# PCBNewLdo.net
KiCad netlist of a schematic drawn in EAGLE
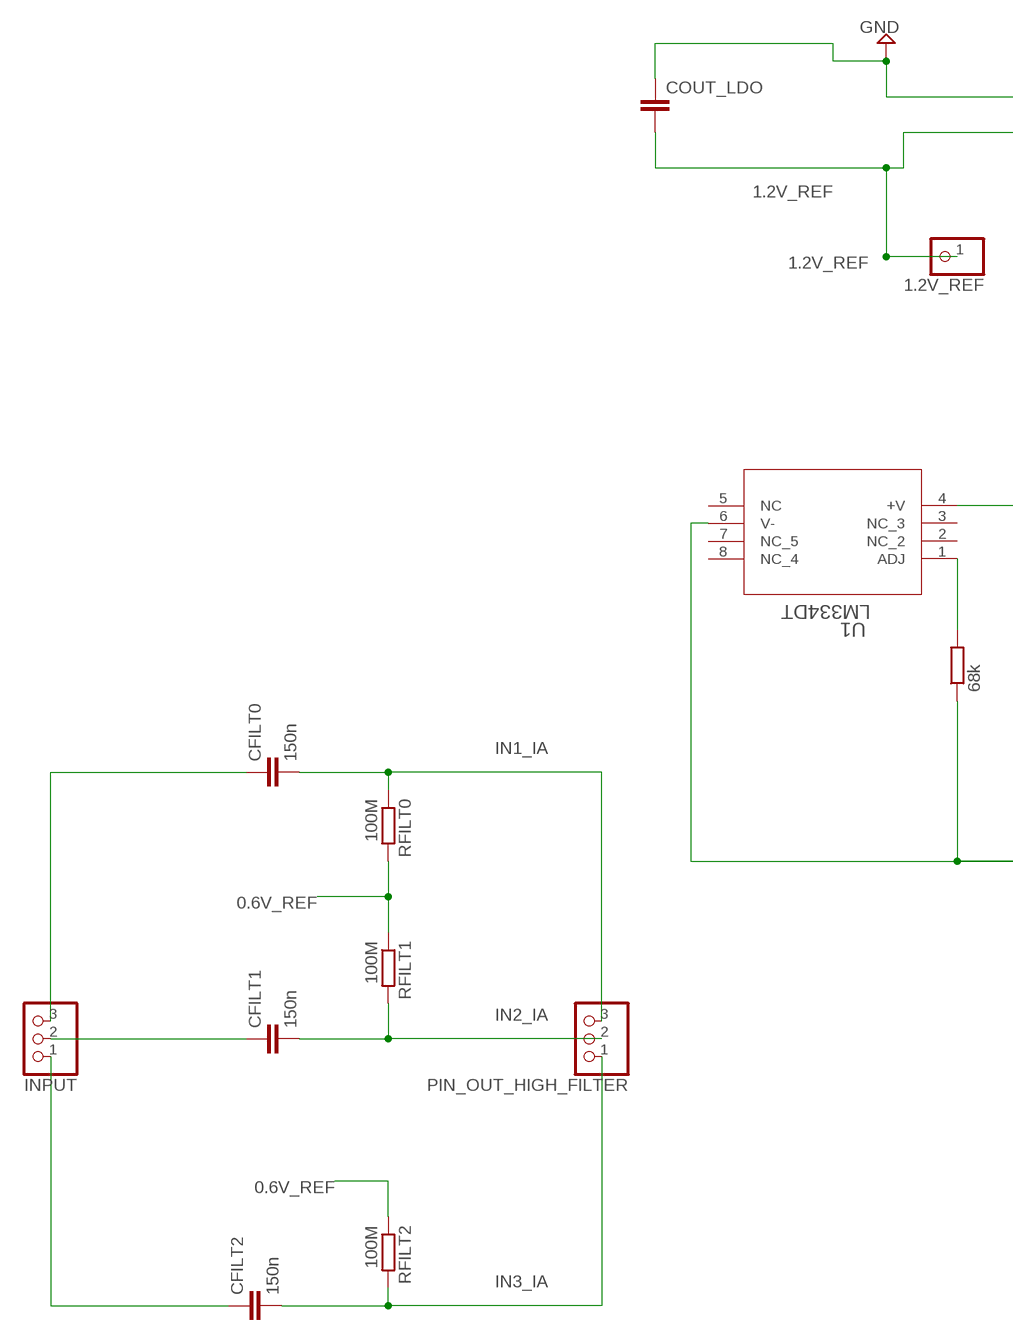
[diagram p0: schematic, sheet 1, part 1 of 2]
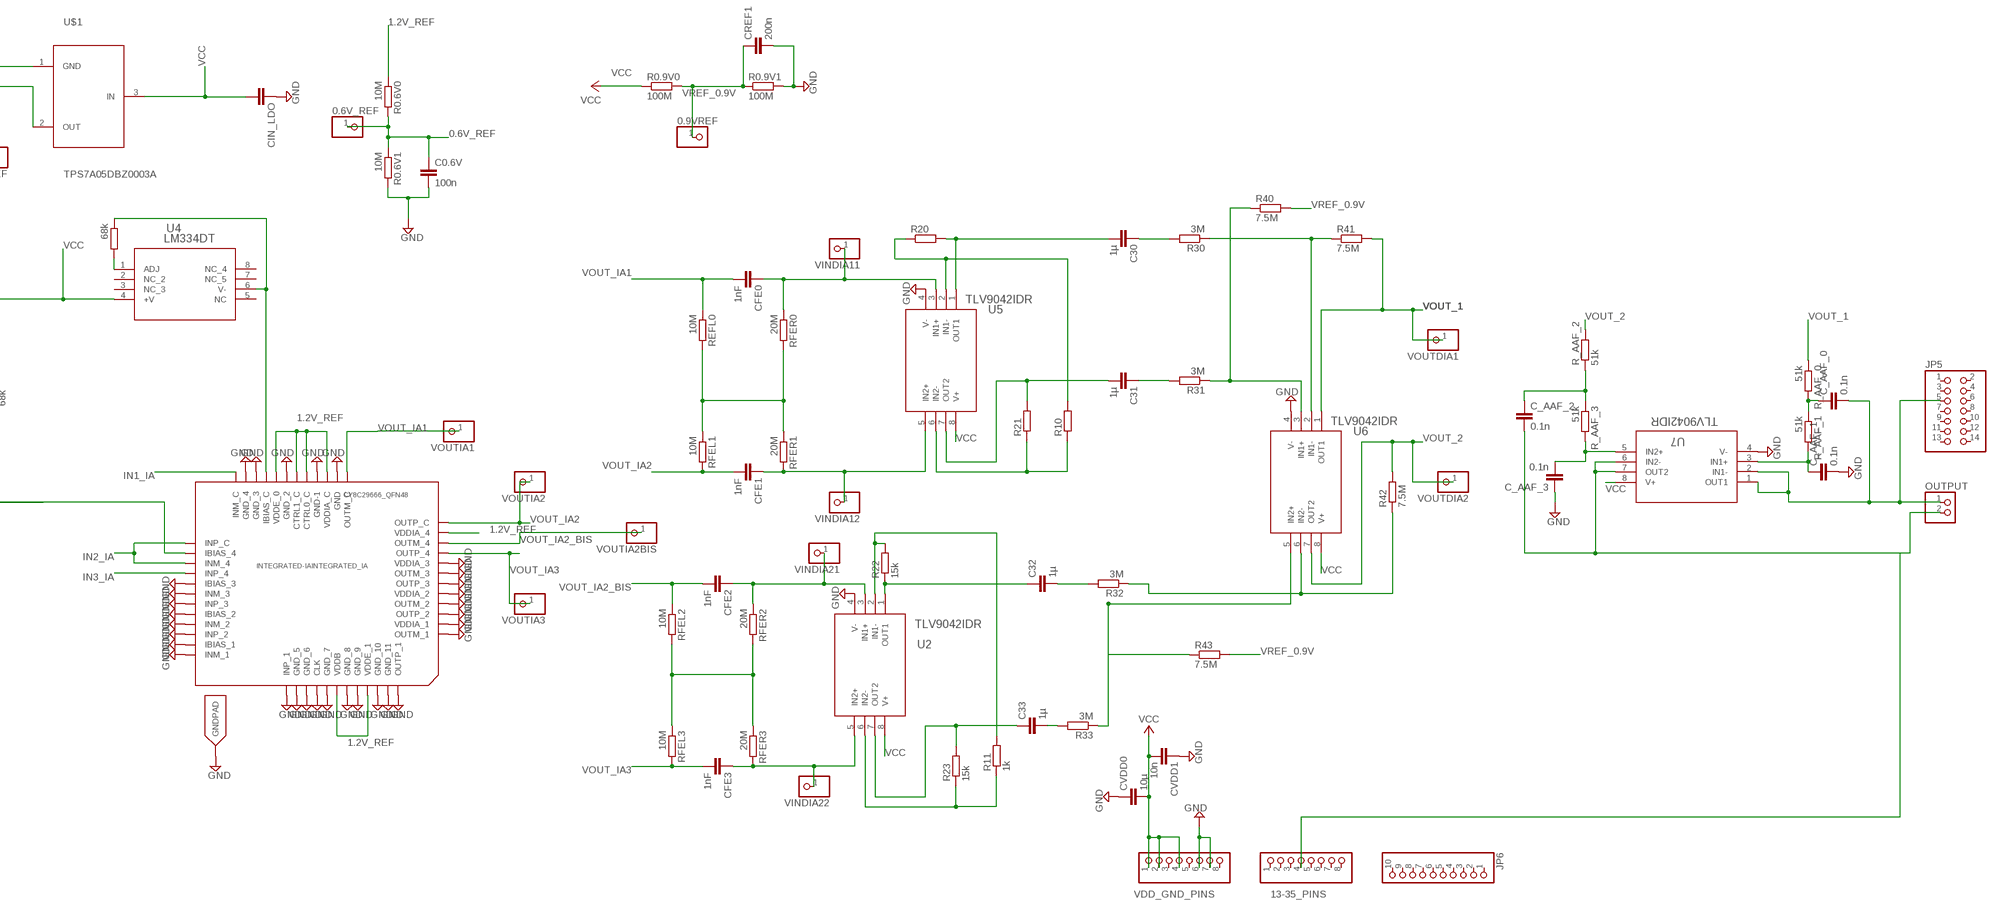
[diagram p1: schematic, sheet 1, part 2 of 2]

(export (version "E")
  (design (tool "Eeschema 10.0.6"))
  (components
    (comp (ref "0.6V_REF")
      (value "PINHD-1X1")
      (footprint "eagle-import:1X01")
      (libsource (lib "eagle-import") (part "PINHD-1X1"))
    )
    (comp (ref "0.9VREF")
      (value "PINHD-1X1")
      (footprint "eagle-import:1X01")
      (libsource (lib "eagle-import") (part "PINHD-1X1"))
    )
    (comp (ref "1.2V_REF")
      (value "PINHD-1X1")
      (footprint "eagle-import:1X01")
      (libsource (lib "eagle-import") (part "PINHD-1X1"))
    )
    (comp (ref "13-35_PINS")
      (value "PINHD-1X8")
      (footprint "eagle-import:1X08")
      (libsource (lib "eagle-import") (part "PINHD-1X8"))
    )
    (comp (ref "C0.6V")
      (value "100n")
      (footprint "eagle-import:C0603")
      (libsource (lib "eagle-import") (part "C-EUC0603"))
    )
    (comp (ref "C30")
      (value "1µ")
      (footprint "eagle-import:C0603")
      (libsource (lib "eagle-import") (part "C-EUC0603"))
    )
    (comp (ref "C31")
      (value "1µ")
      (footprint "eagle-import:C0603")
      (libsource (lib "eagle-import") (part "C-EUC0603"))
    )
    (comp (ref "C32")
      (value "1µ")
      (footprint "eagle-import:C0603")
      (libsource (lib "eagle-import") (part "C-EUC0603"))
    )
    (comp (ref "C33")
      (value "1µ")
      (footprint "eagle-import:C0603")
      (libsource (lib "eagle-import") (part "C-EUC0603"))
    )
    (comp (ref "CFE0")
      (value "1nF")
      (footprint "eagle-import:C0603")
      (libsource (lib "eagle-import") (part "C-EUC0603"))
    )
    (comp (ref "CFE1")
      (value "1nF")
      (footprint "eagle-import:C0603")
      (libsource (lib "eagle-import") (part "C-EUC0603"))
    )
    (comp (ref "CFE2")
      (value "1nF")
      (footprint "eagle-import:C0603")
      (libsource (lib "eagle-import") (part "C-EUC0603"))
    )
    (comp (ref "CFE3")
      (value "1nF")
      (footprint "eagle-import:C0603")
      (libsource (lib "eagle-import") (part "C-EUC0603"))
    )
    (comp (ref "CFILT0")
      (value "150n")
      (footprint "eagle-import:C0603")
      (libsource (lib "eagle-import") (part "C-EUC0603"))
    )
    (comp (ref "CFILT1")
      (value "150n")
      (footprint "eagle-import:C0603")
      (libsource (lib "eagle-import") (part "C-EUC0603"))
    )
    (comp (ref "CFILT2")
      (value "150n")
      (footprint "eagle-import:C0603")
      (libsource (lib "eagle-import") (part "C-EUC0603"))
    )
    (comp (ref "CIN_LDO")
      (value "1µ")
      (footprint "eagle-import:C0603")
      (libsource (lib "eagle-import") (part "C-EUC0603"))
    )
    (comp (ref "COUT_LDO")
      (value "4.7µ")
      (footprint "eagle-import:C0603")
      (libsource (lib "eagle-import") (part "C-EUC0603"))
    )
    (comp (ref "CREF1")
      (value "200n")
      (footprint "eagle-import:C0603")
      (libsource (lib "eagle-import") (part "C-EUC0603"))
    )
    (comp (ref "CVDD0")
      (value "10µ")
      (footprint "eagle-import:C0603")
      (libsource (lib "eagle-import") (part "C-EUC0603"))
    )
    (comp (ref "CVDD1")
      (value "10n")
      (footprint "eagle-import:C0603")
      (libsource (lib "eagle-import") (part "C-EUC0603"))
    )
    (comp (ref "C_AAF_0")
      (value "0.1n")
      (footprint "eagle-import:C0603")
      (libsource (lib "eagle-import") (part "C-EUC0603"))
    )
    (comp (ref "C_AAF_1")
      (value "0.1n")
      (footprint "eagle-import:C0603")
      (libsource (lib "eagle-import") (part "C-EUC0603"))
    )
    (comp (ref "C_AAF_2")
      (value "0.1n")
      (footprint "eagle-import:C0603")
      (libsource (lib "eagle-import") (part "C-EUC0603"))
    )
    (comp (ref "C_AAF_3")
      (value "0.1n")
      (footprint "eagle-import:C0603")
      (libsource (lib "eagle-import") (part "C-EUC0603"))
    )
    (comp (ref "INPUT")
      (value "PINHD-1X3")
      (footprint "eagle-import:1X03")
      (libsource (lib "eagle-import") (part "PINHD-1X3"))
    )
    (comp (ref "INTEGRATED-IA")
      (value "CY8C29666_QFN48")
      (footprint "eagle-import:QFN48")
      (libsource (lib "eagle-import") (part "CY8C29666_QFN48"))
    )
    (comp (ref "JP5")
      (value "PINHD-2X7")
      (footprint "eagle-import:2X07")
      (libsource (lib "eagle-import") (part "PINHD-2X7"))
    )
    (comp (ref "JP6")
      (value "PINHD-1X10")
      (footprint "eagle-import:1X10")
      (libsource (lib "eagle-import") (part "PINHD-1X10"))
    )
    (comp (ref "OUTPUT")
      (value "PINHD-1X2")
      (footprint "eagle-import:1X02")
      (libsource (lib "eagle-import") (part "PINHD-1X2"))
    )
    (comp (ref "PIN_OUT_HIGH_FILTER")
      (value "PINHD-1X3")
      (footprint "eagle-import:1X03")
      (libsource (lib "eagle-import") (part "PINHD-1X3"))
    )
    (comp (ref "R0.6V0")
      (value "10M")
      (footprint "eagle-import:R0603")
      (libsource (lib "eagle-import") (part "R-EU_R0603"))
    )
    (comp (ref "R0.6V1")
      (value "10M")
      (footprint "eagle-import:R0603")
      (libsource (lib "eagle-import") (part "R-EU_R0603"))
    )
    (comp (ref "R0.9V0")
      (value "100M")
      (footprint "eagle-import:R0603")
      (libsource (lib "eagle-import") (part "R-EU_R0603"))
    )
    (comp (ref "R0.9V1")
      (value "100M")
      (footprint "eagle-import:R0603")
      (libsource (lib "eagle-import") (part "R-EU_R0603"))
    )
    (comp (ref "R10")
      (value "R-EU_R0603")
      (footprint "eagle-import:R0603")
      (libsource (lib "eagle-import") (part "R-EU_R0603"))
    )
    (comp (ref "R11")
      (value "1k")
      (footprint "eagle-import:R0603")
      (libsource (lib "eagle-import") (part "R-EU_R0603"))
    )
    (comp (ref "R20")
      (value "R-EU_R0603")
      (footprint "eagle-import:R0603")
      (libsource (lib "eagle-import") (part "R-EU_R0603"))
    )
    (comp (ref "R21")
      (value "R-EU_R0603")
      (footprint "eagle-import:R0603")
      (libsource (lib "eagle-import") (part "R-EU_R0603"))
    )
    (comp (ref "R22")
      (value "15k")
      (footprint "eagle-import:R0603")
      (libsource (lib "eagle-import") (part "R-EU_R0603"))
    )
    (comp (ref "R23")
      (value "15k")
      (footprint "eagle-import:R0603")
      (libsource (lib "eagle-import") (part "R-EU_R0603"))
    )
    (comp (ref "R30")
      (value "3M")
      (footprint "eagle-import:R0603")
      (libsource (lib "eagle-import") (part "R-EU_R0603"))
    )
    (comp (ref "R31")
      (value "3M")
      (footprint "eagle-import:R0603")
      (libsource (lib "eagle-import") (part "R-EU_R0603"))
    )
    (comp (ref "R32")
      (value "3M")
      (footprint "eagle-import:R0603")
      (libsource (lib "eagle-import") (part "R-EU_R0603"))
    )
    (comp (ref "R33")
      (value "3M")
      (footprint "eagle-import:R0603")
      (libsource (lib "eagle-import") (part "R-EU_R0603"))
    )
    (comp (ref "R40")
      (value "7.5M")
      (footprint "eagle-import:R0603")
      (libsource (lib "eagle-import") (part "R-EU_R0603"))
    )
    (comp (ref "R41")
      (value "7.5M")
      (footprint "eagle-import:R0603")
      (libsource (lib "eagle-import") (part "R-EU_R0603"))
    )
    (comp (ref "R42")
      (value "7.5M")
      (footprint "eagle-import:R0603")
      (libsource (lib "eagle-import") (part "R-EU_R0603"))
    )
    (comp (ref "R43")
      (value "7.5M")
      (footprint "eagle-import:R0603")
      (libsource (lib "eagle-import") (part "R-EU_R0603"))
    )
    (comp (ref "REFL0")
      (value "10M")
      (footprint "eagle-import:R0603")
      (libsource (lib "eagle-import") (part "R-EU_R0603"))
    )
    (comp (ref "RFEL1")
      (value "10M")
      (footprint "eagle-import:R0603")
      (libsource (lib "eagle-import") (part "R-EU_R0603"))
    )
    (comp (ref "RFEL2")
      (value "10M")
      (footprint "eagle-import:R0603")
      (libsource (lib "eagle-import") (part "R-EU_R0603"))
    )
    (comp (ref "RFEL3")
      (value "10M")
      (footprint "eagle-import:R0603")
      (libsource (lib "eagle-import") (part "R-EU_R0603"))
    )
    (comp (ref "RFER0")
      (value "20M")
      (footprint "eagle-import:R0603")
      (libsource (lib "eagle-import") (part "R-EU_R0603"))
    )
    (comp (ref "RFER1")
      (value "20M")
      (footprint "eagle-import:R0603")
      (libsource (lib "eagle-import") (part "R-EU_R0603"))
    )
    (comp (ref "RFER2")
      (value "20M")
      (footprint "eagle-import:R0603")
      (libsource (lib "eagle-import") (part "R-EU_R0603"))
    )
    (comp (ref "RFER3")
      (value "20M")
      (footprint "eagle-import:R0603")
      (libsource (lib "eagle-import") (part "R-EU_R0603"))
    )
    (comp (ref "RFILT0")
      (value "100M")
      (footprint "eagle-import:R0603")
      (libsource (lib "eagle-import") (part "R-EU_R0603"))
    )
    (comp (ref "RFILT1")
      (value "100M")
      (footprint "eagle-import:R0603")
      (libsource (lib "eagle-import") (part "R-EU_R0603"))
    )
    (comp (ref "RFILT2")
      (value "100M")
      (footprint "eagle-import:R0603")
      (libsource (lib "eagle-import") (part "R-EU_R0603"))
    )
    (comp (ref "RLM334_0")
      (value "68k")
      (footprint "eagle-import:R0603")
      (libsource (lib "eagle-import") (part "R-EU_R0603"))
    )
    (comp (ref "RLM334_1")
      (value "68k")
      (footprint "eagle-import:R0603")
      (libsource (lib "eagle-import") (part "R-EU_R0603"))
    )
    (comp (ref "R_AAF_0")
      (value "51k")
      (footprint "eagle-import:R0603")
      (libsource (lib "eagle-import") (part "R-EU_R0603"))
    )
    (comp (ref "R_AAF_1")
      (value "51k")
      (footprint "eagle-import:R0603")
      (libsource (lib "eagle-import") (part "R-EU_R0603"))
    )
    (comp (ref "R_AAF_2")
      (value "51k")
      (footprint "eagle-import:R0603")
      (libsource (lib "eagle-import") (part "R-EU_R0603"))
    )
    (comp (ref "R_AAF_3")
      (value "51k")
      (footprint "eagle-import:R0603")
      (libsource (lib "eagle-import") (part "R-EU_R0603"))
    )
    (comp (ref "U$1")
      (value "TPS7A05DBZ0003A")
      (footprint "eagle-import:TFE")
      (libsource (lib "eagle-import") (part "TPS7A05DBZ0003A"))
    )
    (comp (ref "U1")
      (value "LM334DT")
      (footprint "eagle-import:SO-8_STM")
      (libsource (lib "eagle-import") (part "LM334DT"))
    )
    (comp (ref "U2")
      (value "TLV9042IDR")
      (footprint "eagle-import:SOIC8_D_TEX")
      (fields (field (name "COPYRIGHT") "Copyright (C) 2018 Accelerated Designs. All rights reserved"))
      (libsource (lib "eagle-import") (part "TLV9042IDR"))
    )
    (comp (ref "U4")
      (value "LM334DT")
      (footprint "eagle-import:SO-8_STM")
      (libsource (lib "eagle-import") (part "LM334DT"))
    )
    (comp (ref "U5")
      (value "TLV9042IDR")
      (footprint "eagle-import:SOIC8_D_TEX")
      (fields (field (name "COPYRIGHT") "Copyright (C) 2018 Accelerated Designs. All rights reserved"))
      (libsource (lib "eagle-import") (part "TLV9042IDR"))
    )
    (comp (ref "U6")
      (value "TLV9042IDR")
      (footprint "eagle-import:SOIC8_D_TEX")
      (fields (field (name "COPYRIGHT") "Copyright (C) 2018 Accelerated Designs. All rights reserved"))
      (libsource (lib "eagle-import") (part "TLV9042IDR"))
    )
    (comp (ref "U7")
      (value "TLV9042IDR")
      (footprint "eagle-import:SOIC8_D_TEX")
      (fields (field (name "COPYRIGHT") "Copyright (C) 2018 Accelerated Designs. All rights reserved"))
      (libsource (lib "eagle-import") (part "TLV9042IDR"))
    )
    (comp (ref "VDD_GND_PINS")
      (value "PINHD-1X8")
      (footprint "eagle-import:1X08")
      (libsource (lib "eagle-import") (part "PINHD-1X8"))
    )
    (comp (ref "VINDIA11")
      (value "PINHD-1X1")
      (footprint "eagle-import:1X01")
      (libsource (lib "eagle-import") (part "PINHD-1X1"))
    )
    (comp (ref "VINDIA12")
      (value "PINHD-1X1")
      (footprint "eagle-import:1X01")
      (libsource (lib "eagle-import") (part "PINHD-1X1"))
    )
    (comp (ref "VINDIA21")
      (value "PINHD-1X1")
      (footprint "eagle-import:1X01")
      (libsource (lib "eagle-import") (part "PINHD-1X1"))
    )
    (comp (ref "VINDIA22")
      (value "PINHD-1X1")
      (footprint "eagle-import:1X01")
      (libsource (lib "eagle-import") (part "PINHD-1X1"))
    )
    (comp (ref "VOUTDIA1")
      (value "PINHD-1X1")
      (footprint "eagle-import:1X01")
      (libsource (lib "eagle-import") (part "PINHD-1X1"))
    )
    (comp (ref "VOUTDIA2")
      (value "PINHD-1X1")
      (footprint "eagle-import:1X01")
      (libsource (lib "eagle-import") (part "PINHD-1X1"))
    )
    (comp (ref "VOUTIA1")
      (value "PINHD-1X1")
      (footprint "eagle-import:1X01")
      (libsource (lib "eagle-import") (part "PINHD-1X1"))
    )
    (comp (ref "VOUTIA2")
      (value "PINHD-1X1")
      (footprint "eagle-import:1X01")
      (libsource (lib "eagle-import") (part "PINHD-1X1"))
    )
    (comp (ref "VOUTIA2BIS")
      (value "PINHD-1X1")
      (footprint "eagle-import:1X01")
      (libsource (lib "eagle-import") (part "PINHD-1X1"))
    )
    (comp (ref "VOUTIA3")
      (value "PINHD-1X1")
      (footprint "eagle-import:1X01")
      (libsource (lib "eagle-import") (part "PINHD-1X1"))
    )
  )
  (nets
    (net (code "1") (name "/0.6V_REF") (class "Default")
      (node (ref "0.6V_REF") (pin "1") (pinfunction "1_1") (pintype "passive"))
      (node (ref "C0.6V") (pin "1") (pinfunction "1_1") (pintype "passive"))
      (node (ref "R0.6V0") (pin "2") (pinfunction "2_2") (pintype "passive"))
      (node (ref "R0.6V1") (pin "1") (pinfunction "1_1") (pintype "passive"))
      (node (ref "RFILT0") (pin "2") (pinfunction "2_2") (pintype "passive"))
      (node (ref "RFILT1") (pin "1") (pinfunction "1_1") (pintype "passive"))
      (node (ref "RFILT2") (pin "1") (pinfunction "1_1") (pintype "passive"))
    )
    (net (code "2") (name "/1.2V_REF") (class "Default")
      (node (ref "1.2V_REF") (pin "1") (pinfunction "1_1") (pintype "passive"))
      (node (ref "COUT_LDO") (pin "2") (pinfunction "2_2") (pintype "passive"))
      (node (ref "INTEGRATED-IA") (pin "11") (pinfunction "VDDIA_4_11") (pintype "bidirectional"))
      (node (ref "INTEGRATED-IA") (pin "15") (pinfunction "VDDIA_C_15") (pintype "bidirectional"))
      (node (ref "INTEGRATED-IA") (pin "17") (pinfunction "CTRL0_C_17") (pintype "bidirectional"))
      (node (ref "INTEGRATED-IA") (pin "18") (pinfunction "CTRL1_C_18") (pintype "power_in"))
      (node (ref "INTEGRATED-IA") (pin "20") (pinfunction "VDDE_0_20") (pintype "bidirectional"))
      (node (ref "INTEGRATED-IA") (pin "42") (pinfunction "VDDB_42") (pintype "power_in"))
      (node (ref "INTEGRATED-IA") (pin "45") (pinfunction "VDDE_1_45") (pintype "bidirectional"))
      (node (ref "R0.6V0") (pin "1") (pinfunction "1_1") (pintype "passive"))
      (node (ref "U$1") (pin "2") (pinfunction "OUT_2") (pintype "bidirectional"))
    )
    (net (code "3") (name "/IN1_IA") (class "Default")
      (node (ref "CFILT0") (pin "2") (pinfunction "2_2") (pintype "passive"))
      (node (ref "INTEGRATED-IA") (pin "24") (pinfunction "INM_C_24") (pintype "bidirectional"))
      (node (ref "PIN_OUT_HIGH_FILTER") (pin "3") (pinfunction "3_3") (pintype "passive"))
      (node (ref "RFILT0") (pin "1") (pinfunction "1_1") (pintype "passive"))
    )
    (net (code "4") (name "/IN2_IA") (class "Default")
      (node (ref "CFILT1") (pin "2") (pinfunction "2_2") (pintype "passive"))
      (node (ref "INTEGRATED-IA") (pin "25") (pinfunction "INP_C_25") (pintype "bidirectional"))
      (node (ref "INTEGRATED-IA") (pin "27") (pinfunction "INM_4_27") (pintype "bidirectional"))
      (node (ref "PIN_OUT_HIGH_FILTER") (pin "2") (pinfunction "2_2") (pintype "passive"))
      (node (ref "RFILT1") (pin "2") (pinfunction "2_2") (pintype "passive"))
    )
    (net (code "5") (name "/IN3_IA") (class "Default")
      (node (ref "CFILT2") (pin "2") (pinfunction "2_2") (pintype "passive"))
      (node (ref "INTEGRATED-IA") (pin "28") (pinfunction "INP_4_28") (pintype "bidirectional"))
      (node (ref "PIN_OUT_HIGH_FILTER") (pin "1") (pinfunction "1_1") (pintype "passive"))
      (node (ref "RFILT2") (pin "2") (pinfunction "2_2") (pintype "passive"))
    )
    (net (code "6") (name "/VOUT_1") (class "Default")
      (node (ref "R41") (pin "2") (pinfunction "2_2") (pintype "passive"))
      (node (ref "R_AAF_0") (pin "1") (pinfunction "1_1") (pintype "passive"))
      (node (ref "U6") (pin "1") (pinfunction "OUT1_1") (pintype "output"))
      (node (ref "VOUTDIA1") (pin "1") (pinfunction "1_1") (pintype "passive"))
    )
    (net (code "7") (name "/VOUT_2") (class "Default")
      (node (ref "R42") (pin "2") (pinfunction "2_2") (pintype "passive"))
      (node (ref "R_AAF_2") (pin "2") (pinfunction "2_2") (pintype "passive"))
      (node (ref "U6") (pin "7") (pinfunction "OUT2_7") (pintype "output"))
      (node (ref "VOUTDIA2") (pin "1") (pinfunction "1_1") (pintype "passive"))
    )
    (net (code "8") (name "/VOUT_IA1") (class "Default")
      (node (ref "CFE0") (pin "2") (pinfunction "2_2") (pintype "passive"))
      (node (ref "INTEGRATED-IA") (pin "13") (pinfunction "OUTM_C_13") (pintype "bidirectional"))
      (node (ref "REFL0") (pin "1") (pinfunction "1_1") (pintype "passive"))
      (node (ref "VOUTIA1") (pin "1") (pinfunction "1_1") (pintype "passive"))
    )
    (net (code "9") (name "/VOUT_IA2") (class "Default")
      (node (ref "CFE1") (pin "2") (pinfunction "2_2") (pintype "passive"))
      (node (ref "INTEGRATED-IA") (pin "12") (pinfunction "OUTP_C_12") (pintype "bidirectional"))
      (node (ref "RFEL1") (pin "2") (pinfunction "2_2") (pintype "passive"))
      (node (ref "VOUTIA2") (pin "1") (pinfunction "1_1") (pintype "passive"))
    )
    (net (code "10") (name "/VOUT_IA2_BIS") (class "Default")
      (node (ref "CFE2") (pin "2") (pinfunction "2_2") (pintype "passive"))
      (node (ref "INTEGRATED-IA") (pin "10") (pinfunction "OUTM_4_10") (pintype "bidirectional"))
      (node (ref "RFEL2") (pin "1") (pinfunction "1_1") (pintype "passive"))
      (node (ref "VOUTIA2BIS") (pin "1") (pinfunction "1_1") (pintype "passive"))
    )
    (net (code "11") (name "/VOUT_IA3") (class "Default")
      (node (ref "CFE3") (pin "2") (pinfunction "2_2") (pintype "passive"))
      (node (ref "INTEGRATED-IA") (pin "9") (pinfunction "OUTP_4_9") (pintype "bidirectional"))
      (node (ref "RFEL3") (pin "2") (pinfunction "2_2") (pintype "passive"))
      (node (ref "VOUTIA3") (pin "1") (pinfunction "1_1") (pintype "passive"))
    )
    (net (code "12") (name "/VREF_0.9V") (class "Default")
      (node (ref "0.9VREF") (pin "1") (pinfunction "1_1") (pintype "passive"))
      (node (ref "CREF1") (pin "1") (pinfunction "1_1") (pintype "passive"))
      (node (ref "R0.9V0") (pin "2") (pinfunction "2_2") (pintype "passive"))
      (node (ref "R0.9V1") (pin "1") (pinfunction "1_1") (pintype "passive"))
      (node (ref "R40") (pin "2") (pinfunction "2_2") (pintype "passive"))
      (node (ref "R43") (pin "2") (pinfunction "2_2") (pintype "passive"))
    )
    (net (code "13") (name "GND") (class "Default")
      (node (ref "C0.6V") (pin "2") (pinfunction "2_2") (pintype "passive"))
      (node (ref "CIN_LDO") (pin "1") (pinfunction "1_1") (pintype "passive"))
      (node (ref "COUT_LDO") (pin "1") (pinfunction "1_1") (pintype "passive"))
      (node (ref "CREF1") (pin "2") (pinfunction "2_2") (pintype "passive"))
      (node (ref "CVDD0") (pin "1") (pinfunction "1_1") (pintype "passive"))
      (node (ref "CVDD1") (pin "1") (pinfunction "1_1") (pintype "passive"))
      (node (ref "C_AAF_1") (pin "2") (pinfunction "2_2") (pintype "passive"))
      (node (ref "C_AAF_3") (pin "1") (pinfunction "1_1") (pintype "passive"))
      (node (ref "INTEGRATED-IA") (pin "1") (pinfunction "OUTM_1_1") (pintype "bidirectional"))
      (node (ref "INTEGRATED-IA") (pin "14") (pinfunction "GND_14") (pintype "bidirectional"))
      (node (ref "INTEGRATED-IA") (pin "16") (pinfunction "GND-1_16") (pintype "bidirectional"))
      (node (ref "INTEGRATED-IA") (pin "19") (pinfunction "GND_2_19") (pintype "bidirectional"))
      (node (ref "INTEGRATED-IA") (pin "2") (pinfunction "VDDIA_1_2") (pintype "bidirectional"))
      (node (ref "INTEGRATED-IA") (pin "22") (pinfunction "GND_3_22") (pintype "bidirectional"))
      (node (ref "INTEGRATED-IA") (pin "23") (pinfunction "GND_4_23") (pintype "bidirectional"))
      (node (ref "INTEGRATED-IA") (pin "29") (pinfunction "IBIAS_3_29") (pintype "bidirectional"))
      (node (ref "INTEGRATED-IA") (pin "3") (pinfunction "OUTP_2_3") (pintype "bidirectional"))
      (node (ref "INTEGRATED-IA") (pin "30") (pinfunction "INM_3_30") (pintype "bidirectional"))
      (node (ref "INTEGRATED-IA") (pin "31") (pinfunction "INP_3_31") (pintype "bidirectional"))
      (node (ref "INTEGRATED-IA") (pin "32") (pinfunction "IBIAS_2_32") (pintype "bidirectional"))
      (node (ref "INTEGRATED-IA") (pin "33") (pinfunction "INM_2_33") (pintype "bidirectional"))
      (node (ref "INTEGRATED-IA") (pin "34") (pinfunction "INP_2_34") (pintype "bidirectional"))
      (node (ref "INTEGRATED-IA") (pin "35") (pinfunction "IBIAS_1_35") (pintype "bidirectional"))
      (node (ref "INTEGRATED-IA") (pin "36") (pinfunction "INM_1_36") (pintype "bidirectional"))
      (node (ref "INTEGRATED-IA") (pin "37") (pinfunction "INP_1_37") (pintype "bidirectional"))
      (node (ref "INTEGRATED-IA") (pin "38") (pinfunction "GND_5_38") (pintype "bidirectional"))
      (node (ref "INTEGRATED-IA") (pin "39") (pinfunction "GND_6_39") (pintype "bidirectional"))
      (node (ref "INTEGRATED-IA") (pin "4") (pinfunction "OUTM_2_4") (pintype "bidirectional"))
      (node (ref "INTEGRATED-IA") (pin "40") (pinfunction "CLK_40") (pintype "bidirectional"))
      (node (ref "INTEGRATED-IA") (pin "41") (pinfunction "GND_7_41") (pintype "bidirectional"))
      (node (ref "INTEGRATED-IA") (pin "43") (pinfunction "GND_8_43") (pintype "bidirectional"))
      (node (ref "INTEGRATED-IA") (pin "44") (pinfunction "GND_9_44") (pintype "bidirectional"))
      (node (ref "INTEGRATED-IA") (pin "46") (pinfunction "GND_10_46") (pintype "bidirectional"))
      (node (ref "INTEGRATED-IA") (pin "47") (pinfunction "GND_11_47") (pintype "bidirectional"))
      (node (ref "INTEGRATED-IA") (pin "48") (pinfunction "OUTP_1_48") (pintype "bidirectional"))
      (node (ref "INTEGRATED-IA") (pin "5") (pinfunction "VDDIA_2_5") (pintype "bidirectional"))
      (node (ref "INTEGRATED-IA") (pin "6") (pinfunction "OUTP_3_6") (pintype "bidirectional"))
      (node (ref "INTEGRATED-IA") (pin "7") (pinfunction "OUTM_3_7") (pintype "power_in"))
      (node (ref "INTEGRATED-IA") (pin "8") (pinfunction "VDDIA_3_8") (pintype "bidirectional"))
      (node (ref "INTEGRATED-IA") (pin "EXP") (pinfunction "GNDPAD_EXP") (pintype "power_in"))
      (node (ref "R0.6V1") (pin "2") (pinfunction "2_2") (pintype "passive"))
      (node (ref "R0.9V1") (pin "2") (pinfunction "2_2") (pintype "passive"))
      (node (ref "U$1") (pin "1") (pinfunction "GND_1") (pintype "bidirectional"))
      (node (ref "U2") (pin "4") (pinfunction "V-_4") (pintype "power_in"))
      (node (ref "U5") (pin "4") (pinfunction "V-_4") (pintype "power_in"))
      (node (ref "U6") (pin "4") (pinfunction "V-_4") (pintype "power_in"))
      (node (ref "U7") (pin "4") (pinfunction "V-_4") (pintype "power_in"))
      (node (ref "VDD_GND_PINS") (pin "6") (pinfunction "6_6") (pintype "passive"))
      (node (ref "VDD_GND_PINS") (pin "7") (pinfunction "7_7") (pintype "passive"))
    )
    (net (code "14") (name "Net-(C30-Pad1)") (class "Default")
      (node (ref "C30") (pin "1") (pinfunction "1_1") (pintype "passive"))
      (node (ref "R30") (pin "2") (pinfunction "2_2") (pintype "passive"))
    )
    (net (code "15") (name "Net-(C31-Pad1)") (class "Default")
      (node (ref "C31") (pin "1") (pinfunction "1_1") (pintype "passive"))
      (node (ref "R31") (pin "2") (pinfunction "2_2") (pintype "passive"))
    )
    (net (code "16") (name "Net-(C32-Pad2)") (class "Default")
      (node (ref "C32") (pin "2") (pinfunction "2_2") (pintype "passive"))
      (node (ref "R32") (pin "2") (pinfunction "2_2") (pintype "passive"))
    )
    (net (code "17") (name "Net-(C33-Pad2)") (class "Default")
      (node (ref "C33") (pin "2") (pinfunction "2_2") (pintype "passive"))
      (node (ref "R33") (pin "2") (pinfunction "2_2") (pintype "passive"))
    )
    (net (code "18") (name "Net-(CFILT0-Pad1)") (class "Default")
      (node (ref "CFILT0") (pin "1") (pinfunction "1_1") (pintype "passive"))
      (node (ref "INPUT") (pin "3") (pinfunction "3_3") (pintype "passive"))
    )
    (net (code "19") (name "Net-(CFILT1-Pad1)") (class "Default")
      (node (ref "CFILT1") (pin "1") (pinfunction "1_1") (pintype "passive"))
      (node (ref "INPUT") (pin "2") (pinfunction "2_2") (pintype "passive"))
    )
    (net (code "20") (name "Net-(CFILT2-Pad1)") (class "Default")
      (node (ref "CFILT2") (pin "1") (pinfunction "1_1") (pintype "passive"))
      (node (ref "INPUT") (pin "1") (pinfunction "1_1") (pintype "passive"))
    )
    (net (code "21") (name "Net-(C_AAF_0-Pad1)") (class "Default")
      (node (ref "C_AAF_0") (pin "1") (pinfunction "1_1") (pintype "passive"))
      (node (ref "R_AAF_0") (pin "2") (pinfunction "2_2") (pintype "passive"))
      (node (ref "R_AAF_1") (pin "1") (pinfunction "1_1") (pintype "passive"))
    )
    (net (code "22") (name "Net-(C_AAF_2-Pad1)") (class "Default")
      (node (ref "C_AAF_2") (pin "1") (pinfunction "1_1") (pintype "passive"))
      (node (ref "R_AAF_2") (pin "1") (pinfunction "1_1") (pintype "passive"))
      (node (ref "R_AAF_3") (pin "1") (pinfunction "1_1") (pintype "passive"))
    )
    (net (code "23") (name "Net-(INTEGRATED-IAB-IBIAS_4)") (class "Default")
      (node (ref "INTEGRATED-IA") (pin "26") (pinfunction "IBIAS_4_26") (pintype "bidirectional"))
      (node (ref "RLM334_1") (pin "1") (pinfunction "1_1") (pintype "passive"))
      (node (ref "U1") (pin "6") (pinfunction "V-_6") (pintype "power_in"))
    )
    (net (code "24") (name "Net-(INTEGRATED-IAB-IBIAS_C)") (class "Default")
      (node (ref "INTEGRATED-IA") (pin "21") (pinfunction "IBIAS_C_21") (pintype "bidirectional"))
      (node (ref "RLM334_0") (pin "1") (pinfunction "1_1") (pintype "passive"))
      (node (ref "U4") (pin "6") (pinfunction "V-_6") (pintype "power_in"))
    )
    (net (code "25") (name "Net-(REFL0-Pad2)") (class "Default")
      (node (ref "REFL0") (pin "2") (pinfunction "2_2") (pintype "passive"))
      (node (ref "RFEL1") (pin "1") (pinfunction "1_1") (pintype "passive"))
      (node (ref "RFER0") (pin "2") (pinfunction "2_2") (pintype "passive"))
      (node (ref "RFER1") (pin "1") (pinfunction "1_1") (pintype "passive"))
    )
    (net (code "26") (name "Net-(RFEL2-Pad2)") (class "Default")
      (node (ref "RFEL2") (pin "2") (pinfunction "2_2") (pintype "passive"))
      (node (ref "RFEL3") (pin "1") (pinfunction "1_1") (pintype "passive"))
      (node (ref "RFER2") (pin "2") (pinfunction "2_2") (pintype "passive"))
      (node (ref "RFER3") (pin "1") (pinfunction "1_1") (pintype "passive"))
    )
    (net (code "27") (name "Net-(U1-ADJ)") (class "Default")
      (node (ref "RLM334_1") (pin "2") (pinfunction "2_2") (pintype "passive"))
      (node (ref "U1") (pin "1") (pinfunction "ADJ_1") (pintype "input"))
    )
    (net (code "28") (name "Net-(U2-IN1+)") (class "Default")
      (node (ref "CFE2") (pin "1") (pinfunction "1_1") (pintype "passive"))
      (node (ref "RFER2") (pin "1") (pinfunction "1_1") (pintype "passive"))
      (node (ref "U2") (pin "3") (pinfunction "IN1+_3") (pintype "input"))
      (node (ref "VINDIA21") (pin "1") (pinfunction "1_1") (pintype "passive"))
    )
    (net (code "29") (name "Net-(U2-IN1-)") (class "Default")
      (node (ref "R11") (pin "2") (pinfunction "2_2") (pintype "passive"))
      (node (ref "R22") (pin "2") (pinfunction "2_2") (pintype "passive"))
      (node (ref "U2") (pin "2") (pinfunction "IN1-_2") (pintype "input"))
    )
    (net (code "30") (name "Net-(U2-IN2+)") (class "Default")
      (node (ref "CFE3") (pin "1") (pinfunction "1_1") (pintype "passive"))
      (node (ref "RFER3") (pin "2") (pinfunction "2_2") (pintype "passive"))
      (node (ref "U2") (pin "5") (pinfunction "IN2+_5") (pintype "input"))
      (node (ref "VINDIA22") (pin "1") (pinfunction "1_1") (pintype "passive"))
    )
    (net (code "31") (name "Net-(U2-IN2-)") (class "Default")
      (node (ref "R11") (pin "1") (pinfunction "1_1") (pintype "passive"))
      (node (ref "R23") (pin "1") (pinfunction "1_1") (pintype "passive"))
      (node (ref "U2") (pin "6") (pinfunction "IN2-_6") (pintype "input"))
    )
    (net (code "32") (name "Net-(U2-OUT1)") (class "Default")
      (node (ref "C32") (pin "1") (pinfunction "1_1") (pintype "passive"))
      (node (ref "R22") (pin "1") (pinfunction "1_1") (pintype "passive"))
      (node (ref "U2") (pin "1") (pinfunction "OUT1_1") (pintype "output"))
    )
    (net (code "33") (name "Net-(U2-OUT2)") (class "Default")
      (node (ref "C33") (pin "1") (pinfunction "1_1") (pintype "passive"))
      (node (ref "R23") (pin "2") (pinfunction "2_2") (pintype "passive"))
      (node (ref "U2") (pin "7") (pinfunction "OUT2_7") (pintype "output"))
    )
    (net (code "34") (name "Net-(U4-ADJ)") (class "Default")
      (node (ref "RLM334_0") (pin "2") (pinfunction "2_2") (pintype "passive"))
      (node (ref "U4") (pin "1") (pinfunction "ADJ_1") (pintype "input"))
    )
    (net (code "35") (name "Net-(U5-IN1+)") (class "Default")
      (node (ref "CFE0") (pin "1") (pinfunction "1_1") (pintype "passive"))
      (node (ref "RFER0") (pin "1") (pinfunction "1_1") (pintype "passive"))
      (node (ref "U5") (pin "3") (pinfunction "IN1+_3") (pintype "input"))
      (node (ref "VINDIA11") (pin "1") (pinfunction "1_1") (pintype "passive"))
    )
    (net (code "36") (name "Net-(U5-IN1-)") (class "Default")
      (node (ref "R10") (pin "2") (pinfunction "2_2") (pintype "passive"))
      (node (ref "R20") (pin "1") (pinfunction "1_1") (pintype "passive"))
      (node (ref "U5") (pin "2") (pinfunction "IN1-_2") (pintype "input"))
    )
    (net (code "37") (name "Net-(U5-IN2+)") (class "Default")
      (node (ref "CFE1") (pin "1") (pinfunction "1_1") (pintype "passive"))
      (node (ref "RFER1") (pin "2") (pinfunction "2_2") (pintype "passive"))
      (node (ref "U5") (pin "5") (pinfunction "IN2+_5") (pintype "input"))
      (node (ref "VINDIA12") (pin "1") (pinfunction "1_1") (pintype "passive"))
    )
    (net (code "38") (name "Net-(U5-IN2-)") (class "Default")
      (node (ref "R10") (pin "1") (pinfunction "1_1") (pintype "passive"))
      (node (ref "R21") (pin "1") (pinfunction "1_1") (pintype "passive"))
      (node (ref "U5") (pin "6") (pinfunction "IN2-_6") (pintype "input"))
    )
    (net (code "39") (name "Net-(U5-OUT1)") (class "Default")
      (node (ref "C30") (pin "2") (pinfunction "2_2") (pintype "passive"))
      (node (ref "R20") (pin "2") (pinfunction "2_2") (pintype "passive"))
      (node (ref "U5") (pin "1") (pinfunction "OUT1_1") (pintype "output"))
    )
    (net (code "40") (name "Net-(U5-OUT2)") (class "Default")
      (node (ref "C31") (pin "2") (pinfunction "2_2") (pintype "passive"))
      (node (ref "R21") (pin "2") (pinfunction "2_2") (pintype "passive"))
      (node (ref "U5") (pin "7") (pinfunction "OUT2_7") (pintype "output"))
    )
    (net (code "41") (name "Net-(U6-IN1+)") (class "Default")
      (node (ref "R31") (pin "1") (pinfunction "1_1") (pintype "passive"))
      (node (ref "R40") (pin "1") (pinfunction "1_1") (pintype "passive"))
      (node (ref "U6") (pin "3") (pinfunction "IN1+_3") (pintype "input"))
    )
    (net (code "42") (name "Net-(U6-IN1-)") (class "Default")
      (node (ref "R30") (pin "1") (pinfunction "1_1") (pintype "passive"))
      (node (ref "R41") (pin "1") (pinfunction "1_1") (pintype "passive"))
      (node (ref "U6") (pin "2") (pinfunction "IN1-_2") (pintype "input"))
    )
    (net (code "43") (name "Net-(U6-IN2+)") (class "Default")
      (node (ref "R33") (pin "1") (pinfunction "1_1") (pintype "passive"))
      (node (ref "R43") (pin "1") (pinfunction "1_1") (pintype "passive"))
      (node (ref "U6") (pin "5") (pinfunction "IN2+_5") (pintype "input"))
    )
    (net (code "44") (name "Net-(U6-IN2-)") (class "Default")
      (node (ref "R32") (pin "1") (pinfunction "1_1") (pintype "passive"))
      (node (ref "R42") (pin "1") (pinfunction "1_1") (pintype "passive"))
      (node (ref "U6") (pin "6") (pinfunction "IN2-_6") (pintype "input"))
    )
    (net (code "45") (name "Net-(U7-IN1+)") (class "Default")
      (node (ref "C_AAF_1") (pin "1") (pinfunction "1_1") (pintype "passive"))
      (node (ref "R_AAF_1") (pin "2") (pinfunction "2_2") (pintype "passive"))
      (node (ref "U7") (pin "3") (pinfunction "IN1+_3") (pintype "input"))
    )
    (net (code "46") (name "Net-(U7-IN1-)") (class "Default")
      (node (ref "C_AAF_0") (pin "2") (pinfunction "2_2") (pintype "passive"))
      (node (ref "JP5") (pin "5") (pinfunction "5_5") (pintype "passive"))
      (node (ref "OUTPUT") (pin "1") (pinfunction "1_1") (pintype "passive"))
      (node (ref "U7") (pin "1") (pinfunction "OUT1_1") (pintype "output"))
      (node (ref "U7") (pin "2") (pinfunction "IN1-_2") (pintype "input"))
    )
    (net (code "47") (name "Net-(U7-IN2+)") (class "Default")
      (node (ref "C_AAF_3") (pin "2") (pinfunction "2_2") (pintype "passive"))
      (node (ref "R_AAF_3") (pin "2") (pinfunction "2_2") (pintype "passive"))
      (node (ref "U7") (pin "5") (pinfunction "IN2+_5") (pintype "input"))
    )
    (net (code "48") (name "Net-(U7-IN2-)") (class "Default")
      (node (ref "13-35_PINS") (pin "4") (pinfunction "4_4") (pintype "passive"))
      (node (ref "C_AAF_2") (pin "2") (pinfunction "2_2") (pintype "passive"))
      (node (ref "OUTPUT") (pin "2") (pinfunction "2_2") (pintype "passive"))
      (node (ref "U7") (pin "6") (pinfunction "IN2-_6") (pintype "input"))
      (node (ref "U7") (pin "7") (pinfunction "OUT2_7") (pintype "output"))
    )
    (net (code "49") (name "VCC") (class "Default")
      (node (ref "CIN_LDO") (pin "2") (pinfunction "2_2") (pintype "passive"))
      (node (ref "CVDD0") (pin "2") (pinfunction "2_2") (pintype "passive"))
      (node (ref "CVDD1") (pin "2") (pinfunction "2_2") (pintype "passive"))
      (node (ref "R0.9V0") (pin "1") (pinfunction "1_1") (pintype "passive"))
      (node (ref "U$1") (pin "3") (pinfunction "IN_3") (pintype "bidirectional"))
      (node (ref "U1") (pin "4") (pinfunction "+V_4") (pintype "power_in"))
      (node (ref "U2") (pin "8") (pinfunction "V+_8") (pintype "power_in"))
      (node (ref "U4") (pin "4") (pinfunction "+V_4") (pintype "power_in"))
      (node (ref "U5") (pin "8") (pinfunction "V+_8") (pintype "power_in"))
      (node (ref "U6") (pin "8") (pinfunction "V+_8") (pintype "power_in"))
      (node (ref "U7") (pin "8") (pinfunction "V+_8") (pintype "power_in"))
      (node (ref "VDD_GND_PINS") (pin "1") (pinfunction "1_1") (pintype "passive"))
      (node (ref "VDD_GND_PINS") (pin "2") (pinfunction "2_2") (pintype "passive"))
      (node (ref "VDD_GND_PINS") (pin "4") (pinfunction "4_4") (pintype "passive"))
    )
    (net (code "50") (name "unconnected-(13-35_PINS-Pad1)") (class "Default")
      (node (ref "13-35_PINS") (pin "1") (pinfunction "1_1") (pintype "passive"))
    )
    (net (code "51") (name "unconnected-(13-35_PINS-Pad2)") (class "Default")
      (node (ref "13-35_PINS") (pin "2") (pinfunction "2_2") (pintype "passive"))
    )
    (net (code "52") (name "unconnected-(13-35_PINS-Pad3)") (class "Default")
      (node (ref "13-35_PINS") (pin "3") (pinfunction "3_3") (pintype "passive"))
    )
    (net (code "53") (name "unconnected-(13-35_PINS-Pad5)") (class "Default")
      (node (ref "13-35_PINS") (pin "5") (pinfunction "5_5") (pintype "passive"))
    )
    (net (code "54") (name "unconnected-(13-35_PINS-Pad6)") (class "Default")
      (node (ref "13-35_PINS") (pin "6") (pinfunction "6_6") (pintype "passive"))
    )
    (net (code "55") (name "unconnected-(13-35_PINS-Pad7)") (class "Default")
      (node (ref "13-35_PINS") (pin "7") (pinfunction "7_7") (pintype "passive"))
    )
    (net (code "56") (name "unconnected-(13-35_PINS-Pad8)") (class "Default")
      (node (ref "13-35_PINS") (pin "8") (pinfunction "8_8") (pintype "passive"))
    )
    (net (code "57") (name "unconnected-(JP5-Pad1)") (class "Default")
      (node (ref "JP5") (pin "1") (pinfunction "1_1") (pintype "passive"))
    )
    (net (code "58") (name "unconnected-(JP5-Pad2)") (class "Default")
      (node (ref "JP5") (pin "2") (pinfunction "2_2") (pintype "passive"))
    )
    (net (code "59") (name "unconnected-(JP5-Pad3)") (class "Default")
      (node (ref "JP5") (pin "3") (pinfunction "3_3") (pintype "passive"))
    )
    (net (code "60") (name "unconnected-(JP5-Pad4)") (class "Default")
      (node (ref "JP5") (pin "4") (pinfunction "4_4") (pintype "passive"))
    )
    (net (code "61") (name "unconnected-(JP5-Pad6)") (class "Default")
      (node (ref "JP5") (pin "6") (pinfunction "6_6") (pintype "passive"))
    )
    (net (code "62") (name "unconnected-(JP5-Pad7)") (class "Default")
      (node (ref "JP5") (pin "7") (pinfunction "7_7") (pintype "passive"))
    )
    (net (code "63") (name "unconnected-(JP5-Pad8)") (class "Default")
      (node (ref "JP5") (pin "8") (pinfunction "8_8") (pintype "passive"))
    )
    (net (code "64") (name "unconnected-(JP5-Pad9)") (class "Default")
      (node (ref "JP5") (pin "9") (pinfunction "9_9") (pintype "passive"))
    )
    (net (code "65") (name "unconnected-(JP5-Pad10)") (class "Default")
      (node (ref "JP5") (pin "10") (pinfunction "10_10") (pintype "passive"))
    )
    (net (code "66") (name "unconnected-(JP5-Pad11)") (class "Default")
      (node (ref "JP5") (pin "11") (pinfunction "11_11") (pintype "passive"))
    )
    (net (code "67") (name "unconnected-(JP5-Pad12)") (class "Default")
      (node (ref "JP5") (pin "12") (pinfunction "12_12") (pintype "passive"))
    )
    (net (code "68") (name "unconnected-(JP5-Pad13)") (class "Default")
      (node (ref "JP5") (pin "13") (pinfunction "13_13") (pintype "passive"))
    )
    (net (code "69") (name "unconnected-(JP5-Pad14)") (class "Default")
      (node (ref "JP5") (pin "14") (pinfunction "14_14") (pintype "passive"))
    )
    (net (code "70") (name "unconnected-(JP6-Pad1)") (class "Default")
      (node (ref "JP6") (pin "1") (pinfunction "1_1") (pintype "passive"))
    )
    (net (code "71") (name "unconnected-(JP6-Pad2)") (class "Default")
      (node (ref "JP6") (pin "2") (pinfunction "2_2") (pintype "passive"))
    )
    (net (code "72") (name "unconnected-(JP6-Pad3)") (class "Default")
      (node (ref "JP6") (pin "3") (pinfunction "3_3") (pintype "passive"))
    )
    (net (code "73") (name "unconnected-(JP6-Pad4)") (class "Default")
      (node (ref "JP6") (pin "4") (pinfunction "4_4") (pintype "passive"))
    )
    (net (code "74") (name "unconnected-(JP6-Pad5)") (class "Default")
      (node (ref "JP6") (pin "5") (pinfunction "5_5") (pintype "passive"))
    )
    (net (code "75") (name "unconnected-(JP6-Pad6)") (class "Default")
      (node (ref "JP6") (pin "6") (pinfunction "6_6") (pintype "passive"))
    )
    (net (code "76") (name "unconnected-(JP6-Pad7)") (class "Default")
      (node (ref "JP6") (pin "7") (pinfunction "7_7") (pintype "passive"))
    )
    (net (code "77") (name "unconnected-(JP6-Pad8)") (class "Default")
      (node (ref "JP6") (pin "8") (pinfunction "8_8") (pintype "passive"))
    )
    (net (code "78") (name "unconnected-(JP6-Pad9)") (class "Default")
      (node (ref "JP6") (pin "9") (pinfunction "9_9") (pintype "passive"))
    )
    (net (code "79") (name "unconnected-(JP6-Pad10)") (class "Default")
      (node (ref "JP6") (pin "10") (pinfunction "10_10") (pintype "passive"))
    )
    (net (code "80") (name "unconnected-(U1-NC-Pad5)") (class "Default")
      (node (ref "U1") (pin "5") (pinfunction "NC_5") (pintype "no_connect"))
    )
    (net (code "81") (name "unconnected-(U1-NC_2-Pad2)") (class "Default")
      (node (ref "U1") (pin "2") (pinfunction "NC_2_2") (pintype "no_connect"))
    )
    (net (code "82") (name "unconnected-(U1-NC_3-Pad3)") (class "Default")
      (node (ref "U1") (pin "3") (pinfunction "NC_3_3") (pintype "no_connect"))
    )
    (net (code "83") (name "unconnected-(U1-NC_4-Pad8)") (class "Default")
      (node (ref "U1") (pin "8") (pinfunction "NC_4_8") (pintype "no_connect"))
    )
    (net (code "84") (name "unconnected-(U1-NC_5-Pad7)") (class "Default")
      (node (ref "U1") (pin "7") (pinfunction "NC_5_7") (pintype "no_connect"))
    )
    (net (code "85") (name "unconnected-(U4-NC-Pad5)") (class "Default")
      (node (ref "U4") (pin "5") (pinfunction "NC_5") (pintype "no_connect"))
    )
    (net (code "86") (name "unconnected-(U4-NC_2-Pad2)") (class "Default")
      (node (ref "U4") (pin "2") (pinfunction "NC_2_2") (pintype "no_connect"))
    )
    (net (code "87") (name "unconnected-(U4-NC_3-Pad3)") (class "Default")
      (node (ref "U4") (pin "3") (pinfunction "NC_3_3") (pintype "no_connect"))
    )
    (net (code "88") (name "unconnected-(U4-NC_4-Pad8)") (class "Default")
      (node (ref "U4") (pin "8") (pinfunction "NC_4_8") (pintype "no_connect"))
    )
    (net (code "89") (name "unconnected-(U4-NC_5-Pad7)") (class "Default")
      (node (ref "U4") (pin "7") (pinfunction "NC_5_7") (pintype "no_connect"))
    )
    (net (code "90") (name "unconnected-(VDD_GND_PINS-Pad3)") (class "Default")
      (node (ref "VDD_GND_PINS") (pin "3") (pinfunction "3_3") (pintype "passive"))
    )
    (net (code "91") (name "unconnected-(VDD_GND_PINS-Pad5)") (class "Default")
      (node (ref "VDD_GND_PINS") (pin "5") (pinfunction "5_5") (pintype "passive"))
    )
    (net (code "92") (name "unconnected-(VDD_GND_PINS-Pad8)") (class "Default")
      (node (ref "VDD_GND_PINS") (pin "8") (pinfunction "8_8") (pintype "passive"))
    )
  )
)
